# untitled.net
KiCad netlist of a schematic drawn in EAGLE
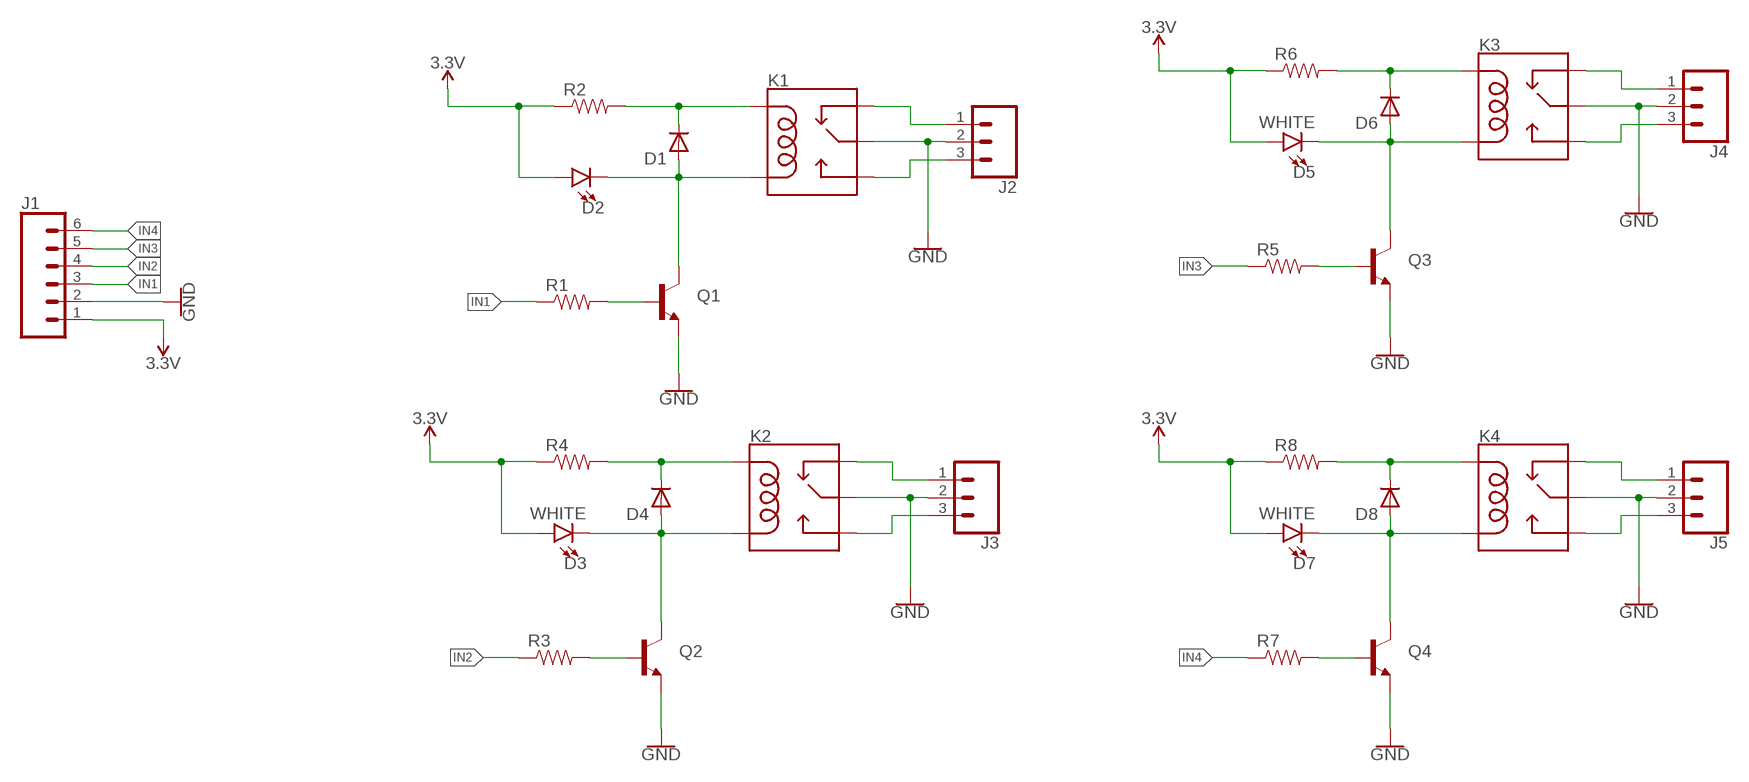
[diagram p0: schematic, sheet 1]

(export (version "E")
  (design (tool "Eeschema 10.0.6"))
  (components
    (comp (ref "D1")
      (value "DIODE-SOD123")
      (footprint "eagle-import:SOD123")
      (libsource (lib "eagle-import") (part "DIODE-SOD123"))
    )
    (comp (ref "D2")
      (value "LED-WHITE1206")
      (footprint "eagle-import:LED-1206")
      (libsource (lib "eagle-import") (part "LED-WHITE1206"))
    )
    (comp (ref "D3")
      (value "WHITE")
      (footprint "eagle-import:LED-1206")
      (libsource (lib "eagle-import") (part "LED-WHITE1206"))
    )
    (comp (ref "D4")
      (value "DIODE-SOD123")
      (footprint "eagle-import:SOD123")
      (libsource (lib "eagle-import") (part "DIODE-SOD123"))
    )
    (comp (ref "D5")
      (value "WHITE")
      (footprint "eagle-import:LED-1206")
      (libsource (lib "eagle-import") (part "LED-WHITE1206"))
    )
    (comp (ref "D6")
      (value "DIODE-SOD123")
      (footprint "eagle-import:SOD123")
      (libsource (lib "eagle-import") (part "DIODE-SOD123"))
    )
    (comp (ref "D7")
      (value "WHITE")
      (footprint "eagle-import:LED-1206")
      (libsource (lib "eagle-import") (part "LED-WHITE1206"))
    )
    (comp (ref "D8")
      (value "DIODE-SOD123")
      (footprint "eagle-import:SOD123")
      (libsource (lib "eagle-import") (part "DIODE-SOD123"))
    )
    (comp (ref "J1")
      (value "CONN_06SILK_FEMALE_PTH")
      (footprint "eagle-import:1X06")
      (libsource (lib "eagle-import") (part "CONN_06SILK_FEMALE_PTH"))
    )
    (comp (ref "J2")
      (value "CONN_03-SCREW-5MM")
      (footprint "eagle-import:SCREWTERMINAL-5MM-3")
      (libsource (lib "eagle-import") (part "CONN_03-SCREW-5MM"))
    )
    (comp (ref "J3")
      (value "CONN_03-SCREW-5MM")
      (footprint "eagle-import:SCREWTERMINAL-5MM-3")
      (libsource (lib "eagle-import") (part "CONN_03-SCREW-5MM"))
    )
    (comp (ref "J4")
      (value "CONN_03-SCREW-5MM")
      (footprint "eagle-import:SCREWTERMINAL-5MM-3")
      (libsource (lib "eagle-import") (part "CONN_03-SCREW-5MM"))
    )
    (comp (ref "J5")
      (value "CONN_03-SCREW-5MM")
      (footprint "eagle-import:SCREWTERMINAL-5MM-3")
      (libsource (lib "eagle-import") (part "CONN_03-SCREW-5MM"))
    )
    (comp (ref "K1")
      (value "RELAY-SPDT")
      (footprint "eagle-import:RELAY_G5LE")
      (libsource (lib "eagle-import") (part "RELAY-SPDT"))
    )
    (comp (ref "K2")
      (value "RELAY-SPDT")
      (footprint "eagle-import:RELAY_G5LE")
      (libsource (lib "eagle-import") (part "RELAY-SPDT"))
    )
    (comp (ref "K3")
      (value "RELAY-SPDT")
      (footprint "eagle-import:RELAY_G5LE")
      (libsource (lib "eagle-import") (part "RELAY-SPDT"))
    )
    (comp (ref "K4")
      (value "RELAY-SPDT")
      (footprint "eagle-import:RELAY_G5LE")
      (libsource (lib "eagle-import") (part "RELAY-SPDT"))
    )
    (comp (ref "Q1")
      (value "TRANSISTOR_NPNSOT89")
      (footprint "eagle-import:SOT89")
      (libsource (lib "eagle-import") (part "TRANSISTOR_NPNSOT89"))
    )
    (comp (ref "Q2")
      (value "TRANSISTOR_NPNSOT89")
      (footprint "eagle-import:SOT89")
      (libsource (lib "eagle-import") (part "TRANSISTOR_NPNSOT89"))
    )
    (comp (ref "Q3")
      (value "TRANSISTOR_NPNSOT89")
      (footprint "eagle-import:SOT89")
      (libsource (lib "eagle-import") (part "TRANSISTOR_NPNSOT89"))
    )
    (comp (ref "Q4")
      (value "TRANSISTOR_NPNSOT89")
      (footprint "eagle-import:SOT89")
      (libsource (lib "eagle-import") (part "TRANSISTOR_NPNSOT89"))
    )
    (comp (ref "R1")
      (value "RESISTOR1206")
      (footprint "eagle-import:1206")
      (libsource (lib "eagle-import") (part "RESISTOR1206"))
    )
    (comp (ref "R2")
      (value "RESISTOR1206")
      (footprint "eagle-import:1206")
      (libsource (lib "eagle-import") (part "RESISTOR1206"))
    )
    (comp (ref "R3")
      (value "RESISTOR1206")
      (footprint "eagle-import:1206")
      (libsource (lib "eagle-import") (part "RESISTOR1206"))
    )
    (comp (ref "R4")
      (value "RESISTOR1206")
      (footprint "eagle-import:1206")
      (libsource (lib "eagle-import") (part "RESISTOR1206"))
    )
    (comp (ref "R5")
      (value "RESISTOR1206")
      (footprint "eagle-import:1206")
      (libsource (lib "eagle-import") (part "RESISTOR1206"))
    )
    (comp (ref "R6")
      (value "RESISTOR1206")
      (footprint "eagle-import:1206")
      (libsource (lib "eagle-import") (part "RESISTOR1206"))
    )
    (comp (ref "R7")
      (value "RESISTOR1206")
      (footprint "eagle-import:1206")
      (libsource (lib "eagle-import") (part "RESISTOR1206"))
    )
    (comp (ref "R8")
      (value "RESISTOR1206")
      (footprint "eagle-import:1206")
      (libsource (lib "eagle-import") (part "RESISTOR1206"))
    )
  )
  (nets
    (net (code "1") (name "3.3V") (class "Default")
      (node (ref "D2") (pin "A") (pinfunction "A_A") (pintype "passive"))
      (node (ref "D3") (pin "A") (pinfunction "A_A") (pintype "passive"))
      (node (ref "D5") (pin "A") (pinfunction "A_A") (pintype "passive"))
      (node (ref "D7") (pin "A") (pinfunction "A_A") (pintype "passive"))
      (node (ref "J1") (pin "1") (pinfunction "1_1") (pintype "passive"))
      (node (ref "R2") (pin "1") (pinfunction "1_1") (pintype "passive"))
      (node (ref "R4") (pin "1") (pinfunction "1_1") (pintype "passive"))
      (node (ref "R6") (pin "1") (pinfunction "1_1") (pintype "passive"))
      (node (ref "R8") (pin "1") (pinfunction "1_1") (pintype "passive"))
    )
    (net (code "2") (name "GND") (class "Default")
      (node (ref "J1") (pin "2") (pinfunction "2_2") (pintype "passive"))
      (node (ref "J2") (pin "2") (pinfunction "2_2") (pintype "passive"))
      (node (ref "J3") (pin "2") (pinfunction "2_2") (pintype "passive"))
      (node (ref "J4") (pin "2") (pinfunction "2_2") (pintype "passive"))
      (node (ref "J5") (pin "2") (pinfunction "2_2") (pintype "passive"))
      (node (ref "K1") (pin "1") (pinfunction "MAIN_1") (pintype "bidirectional"))
      (node (ref "K2") (pin "1") (pinfunction "MAIN_1") (pintype "bidirectional"))
      (node (ref "K3") (pin "1") (pinfunction "MAIN_1") (pintype "bidirectional"))
      (node (ref "K4") (pin "1") (pinfunction "MAIN_1") (pintype "bidirectional"))
      (node (ref "Q1") (pin "3") (pinfunction "E_3") (pintype "passive"))
      (node (ref "Q2") (pin "3") (pinfunction "E_3") (pintype "passive"))
      (node (ref "Q3") (pin "3") (pinfunction "E_3") (pintype "passive"))
      (node (ref "Q4") (pin "3") (pinfunction "E_3") (pintype "passive"))
    )
    (net (code "3") (name "IN1") (class "Default")
      (node (ref "J1") (pin "3") (pinfunction "3_3") (pintype "passive"))
      (node (ref "R1") (pin "1") (pinfunction "1_1") (pintype "passive"))
    )
    (net (code "4") (name "IN2") (class "Default")
      (node (ref "J1") (pin "4") (pinfunction "4_4") (pintype "passive"))
      (node (ref "R3") (pin "1") (pinfunction "1_1") (pintype "passive"))
    )
    (net (code "5") (name "IN3") (class "Default")
      (node (ref "J1") (pin "5") (pinfunction "5_5") (pintype "passive"))
      (node (ref "R5") (pin "1") (pinfunction "1_1") (pintype "passive"))
    )
    (net (code "6") (name "IN4") (class "Default")
      (node (ref "J1") (pin "6") (pinfunction "6_6") (pintype "passive"))
      (node (ref "R7") (pin "1") (pinfunction "1_1") (pintype "passive"))
    )
    (net (code "7") (name "Net-(K1-COIL1)") (class "Default")
      (node (ref "D1") (pin "C") (pinfunction "C_C") (pintype "passive"))
      (node (ref "K1") (pin "2") (pinfunction "COIL1_2") (pintype "bidirectional"))
      (node (ref "R2") (pin "2") (pinfunction "2_2") (pintype "passive"))
    )
    (net (code "8") (name "Net-(K1-COIL2)") (class "Default")
      (node (ref "D1") (pin "A") (pinfunction "A_A") (pintype "passive"))
      (node (ref "D2") (pin "C") (pinfunction "C_C") (pintype "passive"))
      (node (ref "K1") (pin "5") (pinfunction "COIL2_5") (pintype "bidirectional"))
      (node (ref "Q1") (pin "2") (pinfunction "C_2") (pintype "passive"))
    )
    (net (code "9") (name "Net-(K1-NC)") (class "Default")
      (node (ref "J2") (pin "1") (pinfunction "1_1") (pintype "passive"))
      (node (ref "K1") (pin "4") (pinfunction "NC_4") (pintype "bidirectional"))
    )
    (net (code "10") (name "Net-(K1-NO)") (class "Default")
      (node (ref "J2") (pin "3") (pinfunction "3_3") (pintype "passive"))
      (node (ref "K1") (pin "3") (pinfunction "NO_3") (pintype "bidirectional"))
    )
    (net (code "11") (name "Net-(K2-COIL1)") (class "Default")
      (node (ref "D4") (pin "C") (pinfunction "C_C") (pintype "passive"))
      (node (ref "K2") (pin "2") (pinfunction "COIL1_2") (pintype "bidirectional"))
      (node (ref "R4") (pin "2") (pinfunction "2_2") (pintype "passive"))
    )
    (net (code "12") (name "Net-(K2-COIL2)") (class "Default")
      (node (ref "D3") (pin "C") (pinfunction "C_C") (pintype "passive"))
      (node (ref "D4") (pin "A") (pinfunction "A_A") (pintype "passive"))
      (node (ref "K2") (pin "5") (pinfunction "COIL2_5") (pintype "bidirectional"))
      (node (ref "Q2") (pin "2") (pinfunction "C_2") (pintype "passive"))
    )
    (net (code "13") (name "Net-(K2-NC)") (class "Default")
      (node (ref "J3") (pin "1") (pinfunction "1_1") (pintype "passive"))
      (node (ref "K2") (pin "4") (pinfunction "NC_4") (pintype "bidirectional"))
    )
    (net (code "14") (name "Net-(K2-NO)") (class "Default")
      (node (ref "J3") (pin "3") (pinfunction "3_3") (pintype "passive"))
      (node (ref "K2") (pin "3") (pinfunction "NO_3") (pintype "bidirectional"))
    )
    (net (code "15") (name "Net-(K3-COIL1)") (class "Default")
      (node (ref "D6") (pin "C") (pinfunction "C_C") (pintype "passive"))
      (node (ref "K3") (pin "2") (pinfunction "COIL1_2") (pintype "bidirectional"))
      (node (ref "R6") (pin "2") (pinfunction "2_2") (pintype "passive"))
    )
    (net (code "16") (name "Net-(K3-COIL2)") (class "Default")
      (node (ref "D5") (pin "C") (pinfunction "C_C") (pintype "passive"))
      (node (ref "D6") (pin "A") (pinfunction "A_A") (pintype "passive"))
      (node (ref "K3") (pin "5") (pinfunction "COIL2_5") (pintype "bidirectional"))
      (node (ref "Q3") (pin "2") (pinfunction "C_2") (pintype "passive"))
    )
    (net (code "17") (name "Net-(K3-NC)") (class "Default")
      (node (ref "J4") (pin "1") (pinfunction "1_1") (pintype "passive"))
      (node (ref "K3") (pin "4") (pinfunction "NC_4") (pintype "bidirectional"))
    )
    (net (code "18") (name "Net-(K3-NO)") (class "Default")
      (node (ref "J4") (pin "3") (pinfunction "3_3") (pintype "passive"))
      (node (ref "K3") (pin "3") (pinfunction "NO_3") (pintype "bidirectional"))
    )
    (net (code "19") (name "Net-(K4-COIL1)") (class "Default")
      (node (ref "D8") (pin "C") (pinfunction "C_C") (pintype "passive"))
      (node (ref "K4") (pin "2") (pinfunction "COIL1_2") (pintype "bidirectional"))
      (node (ref "R8") (pin "2") (pinfunction "2_2") (pintype "passive"))
    )
    (net (code "20") (name "Net-(K4-COIL2)") (class "Default")
      (node (ref "D7") (pin "C") (pinfunction "C_C") (pintype "passive"))
      (node (ref "D8") (pin "A") (pinfunction "A_A") (pintype "passive"))
      (node (ref "K4") (pin "5") (pinfunction "COIL2_5") (pintype "bidirectional"))
      (node (ref "Q4") (pin "2") (pinfunction "C_2") (pintype "passive"))
    )
    (net (code "21") (name "Net-(K4-NC)") (class "Default")
      (node (ref "J5") (pin "1") (pinfunction "1_1") (pintype "passive"))
      (node (ref "K4") (pin "4") (pinfunction "NC_4") (pintype "bidirectional"))
    )
    (net (code "22") (name "Net-(K4-NO)") (class "Default")
      (node (ref "J5") (pin "3") (pinfunction "3_3") (pintype "passive"))
      (node (ref "K4") (pin "3") (pinfunction "NO_3") (pintype "bidirectional"))
    )
    (net (code "23") (name "Net-(Q1-B)") (class "Default")
      (node (ref "Q1") (pin "1") (pinfunction "B_1") (pintype "passive"))
      (node (ref "R1") (pin "2") (pinfunction "2_2") (pintype "passive"))
    )
    (net (code "24") (name "Net-(Q2-B)") (class "Default")
      (node (ref "Q2") (pin "1") (pinfunction "B_1") (pintype "passive"))
      (node (ref "R3") (pin "2") (pinfunction "2_2") (pintype "passive"))
    )
    (net (code "25") (name "Net-(Q3-B)") (class "Default")
      (node (ref "Q3") (pin "1") (pinfunction "B_1") (pintype "passive"))
      (node (ref "R5") (pin "2") (pinfunction "2_2") (pintype "passive"))
    )
    (net (code "26") (name "Net-(Q4-B)") (class "Default")
      (node (ref "Q4") (pin "1") (pinfunction "B_1") (pintype "passive"))
      (node (ref "R7") (pin "2") (pinfunction "2_2") (pintype "passive"))
    )
  )
)
